# design.net
KiCad netlist of a schematic drawn in Altium Designer
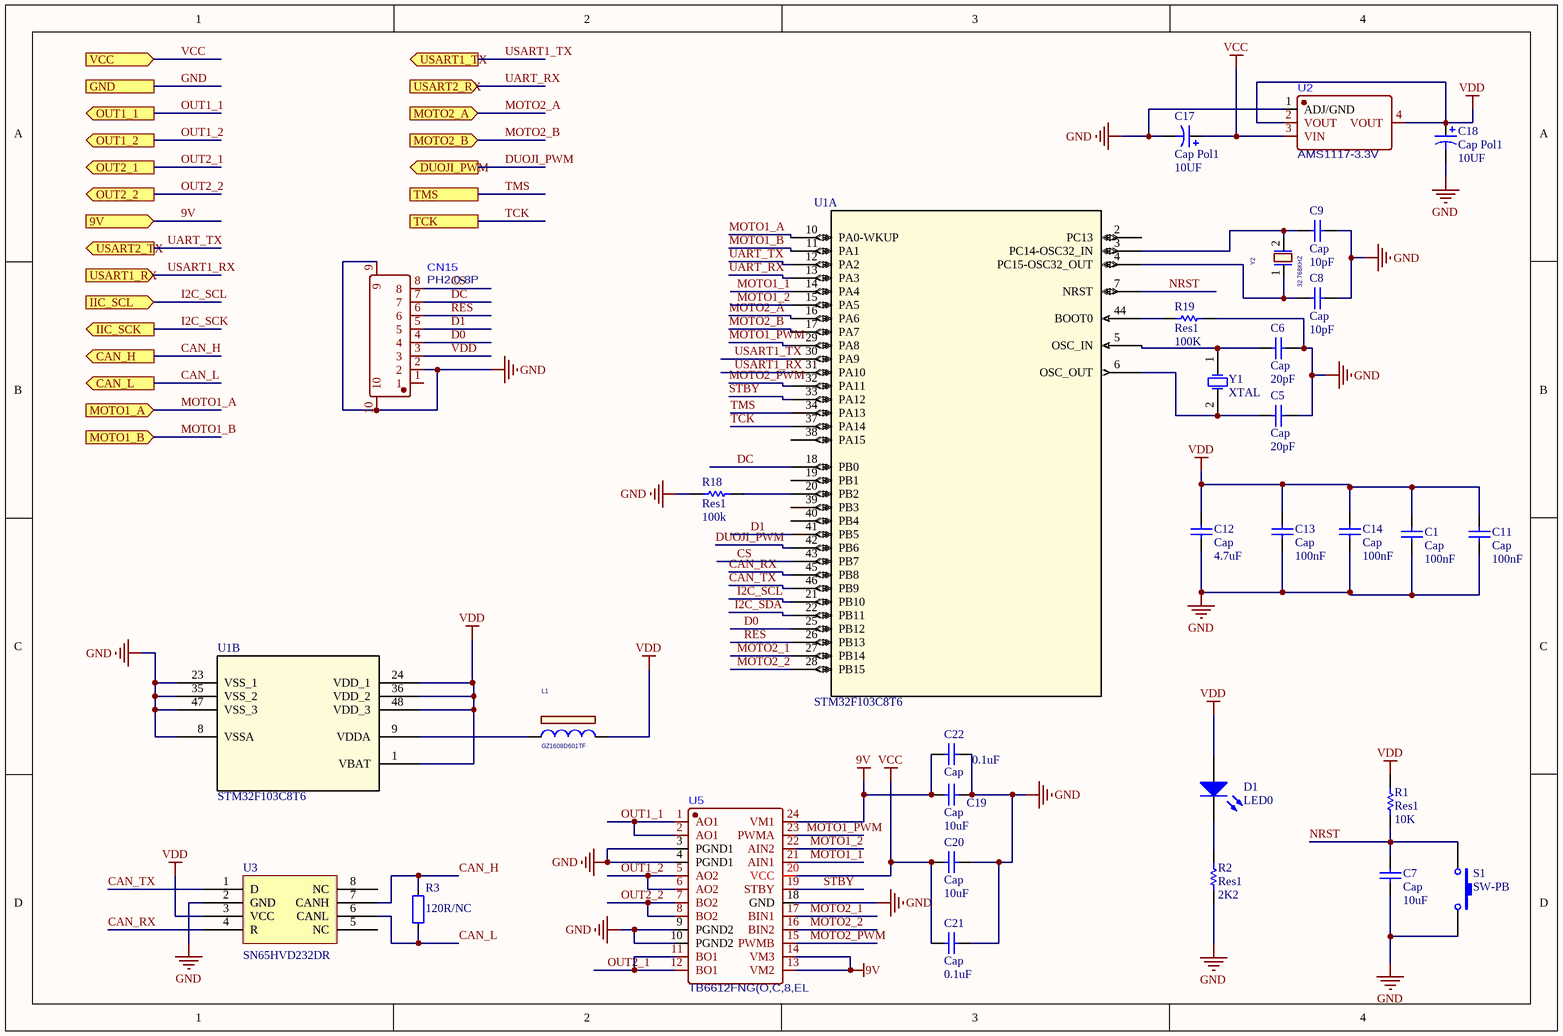
[diagram p0: 主控.SchDoc]

(export (version "E")
  (design (tool "Eeschema 10.0.6"))
  (components
    (comp (ref "C1")
      (value "Cap")
      (footprint "R0603")
      (description "Capacitor")
      (fields (field (name "ALTIUM_VALUE") "100nF") (field (name "PUBLISHER") "Altium Limited"))
      (libsource (lib "Miscellaneous Devices") (part "Cap"))
    )
    (comp (ref "C5")
      (value "Cap")
      (footprint "R0603")
      (description "Capacitor")
      (fields (field (name "ALTIUM_VALUE") "20pF") (field (name "PUBLISHER") "Altium Limited"))
      (libsource (lib "Miscellaneous Devices") (part "Cap"))
    )
    (comp (ref "C6")
      (value "Cap")
      (footprint "R0603")
      (description "Capacitor")
      (fields (field (name "ALTIUM_VALUE") "20pF") (field (name "PUBLISHER") "Altium Limited"))
      (libsource (lib "Miscellaneous Devices") (part "Cap"))
    )
    (comp (ref "C7")
      (value "Cap")
      (footprint "R0603")
      (description "Capacitor")
      (fields (field (name "ALTIUM_VALUE") "10uF") (field (name "PUBLISHER") "Altium Limited"))
      (libsource (lib "Miscellaneous Devices") (part "Cap"))
    )
    (comp (ref "C8")
      (value "Cap")
      (footprint "R0603")
      (description "Capacitor")
      (fields (field (name "ALTIUM_VALUE") "10pF") (field (name "PUBLISHER") "Altium Limited"))
      (libsource (lib "Miscellaneous Devices") (part "Cap"))
    )
    (comp (ref "C9")
      (value "Cap")
      (footprint "R0603")
      (description "Capacitor")
      (fields (field (name "ALTIUM_VALUE") "10pF") (field (name "PUBLISHER") "Altium Limited"))
      (libsource (lib "Miscellaneous Devices") (part "Cap"))
    )
    (comp (ref "C11")
      (value "Cap")
      (footprint "R0603")
      (description "Capacitor")
      (fields (field (name "ALTIUM_VALUE") "100nF") (field (name "PUBLISHER") "Altium Limited"))
      (libsource (lib "Miscellaneous Devices") (part "Cap"))
    )
    (comp (ref "C12")
      (value "Cap")
      (footprint "R0603")
      (description "Capacitor")
      (fields (field (name "ALTIUM_VALUE") "4.7uF") (field (name "PUBLISHER") "Altium Limited"))
      (libsource (lib "Miscellaneous Devices") (part "Cap"))
    )
    (comp (ref "C13")
      (value "Cap")
      (footprint "R0603")
      (description "Capacitor")
      (fields (field (name "ALTIUM_VALUE") "100nF") (field (name "PUBLISHER") "Altium Limited"))
      (libsource (lib "Miscellaneous Devices") (part "Cap"))
    )
    (comp (ref "C14")
      (value "Cap")
      (footprint "R0603")
      (description "Capacitor")
      (fields (field (name "ALTIUM_VALUE") "100nF") (field (name "PUBLISHER") "Altium Limited"))
      (libsource (lib "Miscellaneous Devices") (part "Cap"))
    )
    (comp (ref "C17")
      (value "Cap Pol1")
      (footprint "CAP-SMD_L3.2-W1.6-RD")
      (description "Polarized Capacitor (Radial)")
      (fields (field (name "ALTIUM_VALUE") "10UF") (field (name "PUBLISHER") "Altium Limited"))
      (libsource (lib "Miscellaneous Devices") (part "Cap Pol1"))
    )
    (comp (ref "C18")
      (value "Cap Pol1")
      (footprint "CAP-SMD_L3.2-W1.6-RD")
      (description "Polarized Capacitor (Radial)")
      (fields (field (name "ALTIUM_VALUE") "10UF") (field (name "PUBLISHER") "Altium Limited"))
      (libsource (lib "Miscellaneous Devices") (part "Cap Pol1"))
    )
    (comp (ref "C19")
      (value "Cap")
      (footprint "CAP-SMD_L3.2-W2.8")
      (description "Capacitor")
      (fields (field (name "ALTIUM_VALUE") "10uF") (field (name "PUBLISHER") "Altium Limited"))
      (libsource (lib "Miscellaneous Devices") (part "Cap"))
    )
    (comp (ref "C20")
      (value "Cap")
      (footprint "CAP-SMD_L3.2-W2.8")
      (description "Capacitor")
      (fields (field (name "ALTIUM_VALUE") "10uF") (field (name "PUBLISHER") "Altium Limited"))
      (libsource (lib "Miscellaneous Devices") (part "Cap"))
    )
    (comp (ref "C21")
      (value "Cap")
      (footprint "R0603")
      (description "Capacitor")
      (fields (field (name "ALTIUM_VALUE") "0.1uF") (field (name "PUBLISHER") "Altium Limited"))
      (libsource (lib "Miscellaneous Devices") (part "Cap"))
    )
    (comp (ref "C22")
      (value "Cap")
      (footprint "R0603")
      (description "Capacitor")
      (fields (field (name "ALTIUM_VALUE") "0.1uF") (field (name "PUBLISHER") "Altium Limited"))
      (libsource (lib "Miscellaneous Devices") (part "Cap"))
    )
    (comp (ref "CN15")
      (value "PH2.0-8P")
      (footprint "CONN-SMD_X2016WRS-08-9TSW")
      (libsource (lib "PH2.0-8P_2021-08-20") (part "PH2.0-8P"))
    )
    (comp (ref "D1")
      (value "LED0")
      (footprint "R0603")
      (description "Typical INFRARED GaAs LED")
      (fields (field (name "PUBLISHER") "Altium Limited"))
      (libsource (lib "Miscellaneous Devices") (part "LED0"))
    )
    (comp (ref "L1")
      (value "GZ1608D601TF")
      (description "IND FER BEAD 120 OHM@100MHZ 0.5A 25% 0402")
      (fields (field (name "TOLERANCE") "25%"))
      (libsource (lib "野火_STM32F103C8T6核心板_V1.0_原理图封装库_AD格式") (part "INDUCTOR_FERRITE"))
    )
    (comp (ref "R1")
      (value "Res1")
      (footprint "R0603")
      (description "Resistor")
      (fields (field (name "ALTIUM_VALUE") "10K") (field (name "PUBLISHER") "Altium Limited"))
      (libsource (lib "Miscellaneous Devices") (part "Res1"))
    )
    (comp (ref "R2")
      (value "Res1")
      (footprint "R0603")
      (description "Resistor")
      (fields (field (name "ALTIUM_VALUE") "2K2") (field (name "PUBLISHER") "Altium Limited"))
      (libsource (lib "Miscellaneous Devices") (part "Res1"))
    )
    (comp (ref "R3")
      (value "120R/NC")
      (footprint "R0603")
      (description "Resistor")
      (libsource (lib "MyPcbLib") (part "电阻-0402"))
    )
    (comp (ref "R18")
      (value "Res1")
      (footprint "R0603")
      (description "Resistor")
      (fields (field (name "ALTIUM_VALUE") "100k") (field (name "PUBLISHER") "Altium Limited"))
      (libsource (lib "Miscellaneous Devices") (part "Res1"))
    )
    (comp (ref "R19")
      (value "Res1")
      (footprint "R0603")
      (description "Resistor")
      (fields (field (name "ALTIUM_VALUE") "100K") (field (name "PUBLISHER") "Altium Limited"))
      (libsource (lib "Miscellaneous Devices") (part "Res1"))
    )
    (comp (ref "S1")
      (value "SW-PB")
      (footprint "SW-SMD_L6.1-W3.6-LS7.1")
      (description "Switch")
      (fields (field (name "PUBLISHER") "Altium Limited"))
      (libsource (lib "Miscellaneous Devices") (part "SW-PB"))
    )
    (comp (ref "U1")
      (value "STM32F103C8T6")
      (footprint "LQFP48-7x7mm")
      (description "No Description Available")
      (fields (field (name "COPYRIGHT") "Copyright (C) 2018 Accelerated Designs. All rights reserved"))
      (libsource (lib "STM32F103C8T6") (part "STM32F103C8T6"))
    )
    (comp (ref "U2")
      (value "AMS1117-3.3V")
      (footprint "SOT-223-4_L6.5-W3.5-P2.30-LS7.0-BR")
      (libsource (lib "AMS1117-3.3V_2021-08-31") (part "AMS1117-3.3V"))
    )
    (comp (ref "U3")
      (value "SN65HVD232D")
      (footprint "SOIC-8_L5.0-W4.0-P1.27-LS6.0-BL")
      (fields
        (field (name "MANUFACTURER") "Texas Instruments")
        (field (name "MANUFACTURER PART NUMBER") "SN65HVD232DR")
      )
      (libsource (lib "MyPcbLib") (part "SN65HVD232D"))
    )
    (comp (ref "U5")
      (value "TB6612FNG(O,C,8,EL")
      (footprint "SSOP-24_L8.4-W5.8-P0.65-LS7.8-BL")
      (libsource (lib "TB6612FNG(O,C,8,EL_2021-09-06") (part "TB6612FNG(O,C,8,EL"))
    )
    (comp (ref "Y1")
      (value "XTAL")
      (footprint "OSC-SMD_L11.4-W4.5-LS12.5")
      (description "Crystal Oscillator")
      (fields (field (name "PUBLISHER") "Altium Limited"))
      (libsource (lib "Miscellaneous Devices") (part "XTAL"))
    )
    (comp (ref "Y2")
      (value "32.768KHZ")
      (description "XTAL 32.768KHZ 7PF 20PPM -- SMT")
      (libsource (lib "野火_STM32F103C8T6核心板_V1.0_原理图封装库_AD格式") (part "CRYSTAL"))
    )
  )
  (nets
    (net (code "1") (name "/CAN_H") (class "Default")
      (node (ref "R3") (pin "1") (pinfunction "1_1") (pintype "passive"))
      (node (ref "U3") (pin "7") (pinfunction "CANH_7") (pintype "passive"))
    )
    (net (code "2") (name "/CAN_L") (class "Default")
      (node (ref "R3") (pin "2") (pinfunction "2_2") (pintype "passive"))
      (node (ref "U3") (pin "6") (pinfunction "CANL_6") (pintype "passive"))
    )
    (net (code "3") (name "/CAN_RX") (class "Default")
      (node (ref "U1") (pin "45") (pinfunction "PB8_45") (pintype "bidirectional"))
      (node (ref "U3") (pin "4") (pinfunction "R_4") (pintype "passive"))
    )
    (net (code "4") (name "/CAN_TX") (class "Default")
      (node (ref "U1") (pin "46") (pinfunction "PB9_46") (pintype "bidirectional"))
      (node (ref "U3") (pin "1") (pinfunction "D_1") (pintype "passive"))
    )
    (net (code "5") (name "/CS") (class "Default")
      (node (ref "CN15") (pin "8") (pinfunction "8_8") (pintype "passive"))
      (node (ref "U1") (pin "43") (pinfunction "PB7_43") (pintype "bidirectional"))
    )
    (net (code "6") (name "/D0") (class "Default")
      (node (ref "CN15") (pin "4") (pinfunction "4_4") (pintype "passive"))
      (node (ref "U1") (pin "25") (pinfunction "PB12_25") (pintype "bidirectional"))
    )
    (net (code "7") (name "/D1") (class "Default")
      (node (ref "CN15") (pin "5") (pinfunction "5_5") (pintype "passive"))
      (node (ref "U1") (pin "41") (pinfunction "PB5_41") (pintype "bidirectional"))
    )
    (net (code "8") (name "/DC") (class "Default")
      (node (ref "CN15") (pin "7") (pinfunction "7_7") (pintype "passive"))
      (node (ref "U1") (pin "18") (pinfunction "PB0_18") (pintype "bidirectional"))
    )
    (net (code "9") (name "/DUOJI_PWM") (class "Default")
      (node (ref "U1") (pin "42") (pinfunction "PB6_42") (pintype "bidirectional"))
    )
    (net (code "11") (name "/I2C_SCL") (class "Default")
      (node (ref "U1") (pin "21") (pinfunction "PB10_21") (pintype "bidirectional"))
    )
    (net (code "12") (name "/I2C_SDA") (class "Default")
      (node (ref "U1") (pin "22") (pinfunction "PB11_22") (pintype "bidirectional"))
    )
    (net (code "13") (name "/MOTO1_1") (class "Default")
      (node (ref "U1") (pin "14") (pinfunction "PA4_14") (pintype "bidirectional"))
      (node (ref "U5") (pin "21") (pinfunction "AIN1_21") (pintype "passive"))
    )
    (net (code "14") (name "/MOTO1_2") (class "Default")
      (node (ref "U1") (pin "15") (pinfunction "PA5_15") (pintype "bidirectional"))
      (node (ref "U5") (pin "22") (pinfunction "AIN2_22") (pintype "passive"))
    )
    (net (code "15") (name "/MOTO1_A") (class "Default")
      (node (ref "U1") (pin "10") (pinfunction "PA0-WKUP_10") (pintype "bidirectional"))
    )
    (net (code "16") (name "/MOTO1_B") (class "Default")
      (node (ref "U1") (pin "11") (pinfunction "PA1_11") (pintype "bidirectional"))
    )
    (net (code "17") (name "/MOTO1_PWM") (class "Default")
      (node (ref "U1") (pin "29") (pinfunction "PA8_29") (pintype "bidirectional"))
      (node (ref "U5") (pin "23") (pinfunction "PWMA_23") (pintype "passive"))
    )
    (net (code "18") (name "/MOTO2_1") (class "Default")
      (node (ref "U1") (pin "27") (pinfunction "PB14_27") (pintype "bidirectional"))
      (node (ref "U5") (pin "17") (pinfunction "BIN1_17") (pintype "passive"))
    )
    (net (code "19") (name "/MOTO2_2") (class "Default")
      (node (ref "U1") (pin "28") (pinfunction "PB15_28") (pintype "bidirectional"))
      (node (ref "U5") (pin "16") (pinfunction "BIN2_16") (pintype "passive"))
    )
    (net (code "20") (name "/MOTO2_A") (class "Default")
      (node (ref "U1") (pin "16") (pinfunction "PA6_16") (pintype "bidirectional"))
    )
    (net (code "21") (name "/MOTO2_B") (class "Default")
      (node (ref "U1") (pin "17") (pinfunction "PA7_17") (pintype "bidirectional"))
    )
    (net (code "22") (name "/MOTO2_PWM") (class "Default")
      (node (ref "U1") (pin "32") (pinfunction "PA11_32") (pintype "bidirectional"))
      (node (ref "U5") (pin "15") (pinfunction "PWMB_15") (pintype "passive"))
    )
    (net (code "23") (name "/NRST") (class "Default")
      (node (ref "C7") (pin "2") (pinfunction "2_2") (pintype "passive"))
      (node (ref "R1") (pin "1") (pinfunction "1_1") (pintype "passive"))
      (node (ref "S1") (pin "1") (pinfunction "1_1") (pintype "passive"))
      (node (ref "U1") (pin "7") (pinfunction "NRST_7") (pintype "bidirectional"))
    )
    (net (code "24") (name "/OUT1_1") (class "Default")
      (node (ref "U5") (pin "1") (pinfunction "AO1_1") (pintype "passive"))
      (node (ref "U5") (pin "2") (pinfunction "AO1_2") (pintype "passive"))
    )
    (net (code "25") (name "/OUT1_2") (class "Default")
      (node (ref "U5") (pin "5") (pinfunction "AO2_5") (pintype "passive"))
      (node (ref "U5") (pin "6") (pinfunction "AO2_6") (pintype "passive"))
    )
    (net (code "26") (name "/OUT2_1") (class "Default")
      (node (ref "U5") (pin "11") (pinfunction "BO1_11") (pintype "passive"))
      (node (ref "U5") (pin "12") (pinfunction "BO1_12") (pintype "passive"))
    )
    (net (code "27") (name "/OUT2_2") (class "Default")
      (node (ref "U5") (pin "7") (pinfunction "BO2_7") (pintype "passive"))
      (node (ref "U5") (pin "8") (pinfunction "BO2_8") (pintype "passive"))
    )
    (net (code "28") (name "/RES") (class "Default")
      (node (ref "CN15") (pin "6") (pinfunction "6_6") (pintype "passive"))
      (node (ref "U1") (pin "26") (pinfunction "PB13_26") (pintype "bidirectional"))
    )
    (net (code "29") (name "/STBY") (class "Default")
      (node (ref "U1") (pin "33") (pinfunction "PA12_33") (pintype "bidirectional"))
      (node (ref "U5") (pin "19") (pinfunction "STBY_19") (pintype "passive"))
    )
    (net (code "30") (name "/TCK") (class "Default")
      (node (ref "U1") (pin "37") (pinfunction "PA14_37") (pintype "bidirectional"))
    )
    (net (code "31") (name "/TMS") (class "Default")
      (node (ref "U1") (pin "34") (pinfunction "PA13_34") (pintype "bidirectional"))
    )
    (net (code "32") (name "/UART_RX") (class "Default")
      (node (ref "U1") (pin "13") (pinfunction "PA3_13") (pintype "bidirectional"))
    )
    (net (code "33") (name "/UART_TX") (class "Default")
      (node (ref "U1") (pin "12") (pinfunction "PA2_12") (pintype "bidirectional"))
    )
    (net (code "34") (name "/USART1_RX") (class "Default")
      (node (ref "U1") (pin "31") (pinfunction "PA10_31") (pintype "bidirectional"))
    )
    (net (code "35") (name "/USART1_TX") (class "Default")
      (node (ref "U1") (pin "30") (pinfunction "PA9_30") (pintype "bidirectional"))
    )
    (net (code "36") (name "9V") (class "Default")
      (node (ref "C19") (pin "1") (pinfunction "1_1") (pintype "passive"))
      (node (ref "C22") (pin "1") (pinfunction "1_1") (pintype "passive"))
      (node (ref "U5") (pin "13") (pinfunction "VM2_13") (pintype "passive"))
      (node (ref "U5") (pin "14") (pinfunction "VM3_14") (pintype "passive"))
      (node (ref "U5") (pin "24") (pinfunction "VM1_24") (pintype "passive"))
    )
    (net (code "37") (name "GND") (class "Default")
      (node (ref "C1") (pin "1") (pinfunction "1_1") (pintype "passive"))
      (node (ref "C11") (pin "1") (pinfunction "1_1") (pintype "passive"))
      (node (ref "C12") (pin "1") (pinfunction "1_1") (pintype "passive"))
      (node (ref "C13") (pin "1") (pinfunction "1_1") (pintype "passive"))
      (node (ref "C14") (pin "1") (pinfunction "1_1") (pintype "passive"))
      (node (ref "C17") (pin "2") (pinfunction "2_2") (pintype "passive"))
      (node (ref "C18") (pin "2") (pinfunction "2_2") (pintype "passive"))
      (node (ref "C19") (pin "2") (pinfunction "2_2") (pintype "passive"))
      (node (ref "C20") (pin "2") (pinfunction "2_2") (pintype "passive"))
      (node (ref "C21") (pin "2") (pinfunction "2_2") (pintype "passive"))
      (node (ref "C22") (pin "2") (pinfunction "2_2") (pintype "passive"))
      (node (ref "C5") (pin "1") (pinfunction "1_1") (pintype "passive"))
      (node (ref "C6") (pin "1") (pinfunction "1_1") (pintype "passive"))
      (node (ref "C7") (pin "1") (pinfunction "1_1") (pintype "passive"))
      (node (ref "C8") (pin "1") (pinfunction "1_1") (pintype "passive"))
      (node (ref "C9") (pin "1") (pinfunction "1_1") (pintype "passive"))
      (node (ref "CN15") (pin "10") (pinfunction "10_10") (pintype "passive"))
      (node (ref "CN15") (pin "2") (pinfunction "2_2") (pintype "passive"))
      (node (ref "CN15") (pin "9") (pinfunction "9_9") (pintype "passive"))
      (node (ref "R18") (pin "1") (pinfunction "1_1") (pintype "passive"))
      (node (ref "R19") (pin "2") (pinfunction "2_2") (pintype "passive"))
      (node (ref "R2") (pin "2") (pinfunction "2_2") (pintype "passive"))
      (node (ref "S1") (pin "2") (pinfunction "2_2") (pintype "passive"))
      (node (ref "U1") (pin "23") (pinfunction "VSS_1_23") (pintype "power_in"))
      (node (ref "U1") (pin "35") (pinfunction "VSS_2_35") (pintype "power_in"))
      (node (ref "U1") (pin "47") (pinfunction "VSS_3_47") (pintype "power_in"))
      (node (ref "U1") (pin "8") (pinfunction "VSSA_8") (pintype "power_in"))
      (node (ref "U2") (pin "1") (pinfunction "ADJ/GND_1") (pintype "passive"))
      (node (ref "U3") (pin "2") (pinfunction "GND_2") (pintype "passive"))
      (node (ref "U5") (pin "10") (pinfunction "PGND2_10") (pintype "passive"))
      (node (ref "U5") (pin "18") (pinfunction "GND_18") (pintype "passive"))
      (node (ref "U5") (pin "3") (pinfunction "PGND1_3") (pintype "passive"))
      (node (ref "U5") (pin "4") (pinfunction "PGND1_4") (pintype "passive"))
      (node (ref "U5") (pin "9") (pinfunction "PGND2_9") (pintype "passive"))
    )
    (net (code "38") (name "Net-(D1-K)") (class "Default")
      (node (ref "D1") (pin "2") (pinfunction "K_2") (pintype "passive"))
      (node (ref "R2") (pin "1") (pinfunction "1_1") (pintype "passive"))
    )
    (net (code "39") (name "Net-(U1A-BOOT0)") (class "Default")
      (node (ref "R19") (pin "1") (pinfunction "1_1") (pintype "passive"))
      (node (ref "U1") (pin "44") (pinfunction "BOOT0_44") (pintype "input"))
    )
    (net (code "40") (name "Net-(U1A-OSC_IN)") (class "Default")
      (node (ref "C6") (pin "2") (pinfunction "2_2") (pintype "passive"))
      (node (ref "U1") (pin "5") (pinfunction "OSC_IN_5") (pintype "input"))
      (node (ref "Y1") (pin "1") (pinfunction "OSC1_1") (pintype "passive"))
    )
    (net (code "41") (name "Net-(U1A-OSC_OUT)") (class "Default")
      (node (ref "C5") (pin "2") (pinfunction "2_2") (pintype "passive"))
      (node (ref "U1") (pin "6") (pinfunction "OSC_OUT_6") (pintype "output"))
      (node (ref "Y1") (pin "2") (pinfunction "OSC2_2") (pintype "passive"))
    )
    (net (code "42") (name "Net-(U1A-PB2)") (class "Default")
      (node (ref "R18") (pin "2") (pinfunction "2_2") (pintype "passive"))
      (node (ref "U1") (pin "20") (pinfunction "PB2_20") (pintype "bidirectional"))
    )
    (net (code "43") (name "Net-(U1A-PC14-OSC32_IN)") (class "Default")
      (node (ref "C9") (pin "2") (pinfunction "2_2") (pintype "passive"))
      (node (ref "U1") (pin "3") (pinfunction "PC14-OSC32_IN_3") (pintype "bidirectional"))
      (node (ref "Y2") (pin "2") (pinfunction "2_2") (pintype "passive"))
    )
    (net (code "44") (name "Net-(U1A-PC15-OSC32_OUT)") (class "Default")
      (node (ref "C8") (pin "2") (pinfunction "2_2") (pintype "passive"))
      (node (ref "U1") (pin "4") (pinfunction "PC15-OSC32_OUT_4") (pintype "bidirectional"))
      (node (ref "Y2") (pin "1") (pinfunction "1_1") (pintype "passive"))
    )
    (net (code "45") (name "Net-(U1B-VDDA)") (class "Default")
      (node (ref "L1") (pin "1") (pinfunction "1_1") (pintype "passive"))
      (node (ref "U1") (pin "9") (pinfunction "VDDA_9") (pintype "power_in"))
    )
    (net (code "46") (name "VCC") (class "Default")
      (node (ref "C17") (pin "1") (pinfunction "1_1") (pintype "passive"))
      (node (ref "C20") (pin "1") (pinfunction "1_1") (pintype "passive"))
      (node (ref "C21") (pin "1") (pinfunction "1_1") (pintype "passive"))
      (node (ref "U2") (pin "3") (pinfunction "VIN_3") (pintype "passive"))
      (node (ref "U5") (pin "20") (pinfunction "VCC_20") (pintype "passive"))
    )
    (net (code "47") (name "VDD") (class "Default")
      (node (ref "C1") (pin "2") (pinfunction "2_2") (pintype "passive"))
      (node (ref "C11") (pin "2") (pinfunction "2_2") (pintype "passive"))
      (node (ref "C12") (pin "2") (pinfunction "2_2") (pintype "passive"))
      (node (ref "C13") (pin "2") (pinfunction "2_2") (pintype "passive"))
      (node (ref "C14") (pin "2") (pinfunction "2_2") (pintype "passive"))
      (node (ref "C18") (pin "1") (pinfunction "1_1") (pintype "passive"))
      (node (ref "CN15") (pin "3") (pinfunction "3_3") (pintype "passive"))
      (node (ref "D1") (pin "1") (pinfunction "A_1") (pintype "passive"))
      (node (ref "L1") (pin "2") (pinfunction "2_2") (pintype "passive"))
      (node (ref "R1") (pin "2") (pinfunction "2_2") (pintype "passive"))
      (node (ref "U1") (pin "1") (pinfunction "VBAT_1") (pintype "power_in"))
      (node (ref "U1") (pin "24") (pinfunction "VDD_1_24") (pintype "power_in"))
      (node (ref "U1") (pin "36") (pinfunction "VDD_2_36") (pintype "power_in"))
      (node (ref "U1") (pin "48") (pinfunction "VDD_3_48") (pintype "power_in"))
      (node (ref "U2") (pin "2") (pinfunction "VOUT_2") (pintype "passive"))
      (node (ref "U2") (pin "4") (pinfunction "VOUT_4") (pintype "passive"))
      (node (ref "U3") (pin "3") (pinfunction "VCC_3") (pintype "passive"))
    )
    (net (code "48") (name "unconnected-(CN15-Pad1)") (class "Default")
      (node (ref "CN15") (pin "1") (pinfunction "1_1") (pintype "passive"))
    )
    (net (code "49") (name "unconnected-(U1A-PA15-Pad38)") (class "Default")
      (node (ref "U1") (pin "38") (pinfunction "PA15_38") (pintype "bidirectional"))
    )
    (net (code "50") (name "unconnected-(U1A-PB1-Pad19)") (class "Default")
      (node (ref "U1") (pin "19") (pinfunction "PB1_19") (pintype "bidirectional"))
    )
    (net (code "51") (name "unconnected-(U1A-PB3-Pad39)") (class "Default")
      (node (ref "U1") (pin "39") (pinfunction "PB3_39") (pintype "bidirectional"))
    )
    (net (code "52") (name "unconnected-(U1A-PB4-Pad40)") (class "Default")
      (node (ref "U1") (pin "40") (pinfunction "PB4_40") (pintype "bidirectional"))
    )
    (net (code "53") (name "unconnected-(U1A-PC13-Pad2)") (class "Default")
      (node (ref "U1") (pin "2") (pinfunction "PC13_2") (pintype "bidirectional"))
    )
    (net (code "54") (name "unconnected-(U3-NC-Pad5)") (class "Default")
      (node (ref "U3") (pin "5") (pinfunction "NC_5") (pintype "passive"))
    )
    (net (code "55") (name "unconnected-(U3-NC-Pad8)") (class "Default")
      (node (ref "U3") (pin "8") (pinfunction "NC_8") (pintype "passive"))
    )
  )
)
